# joint_board_boosterpack_can.net
KiCad netlist of a schematic drawn in Altium Designer
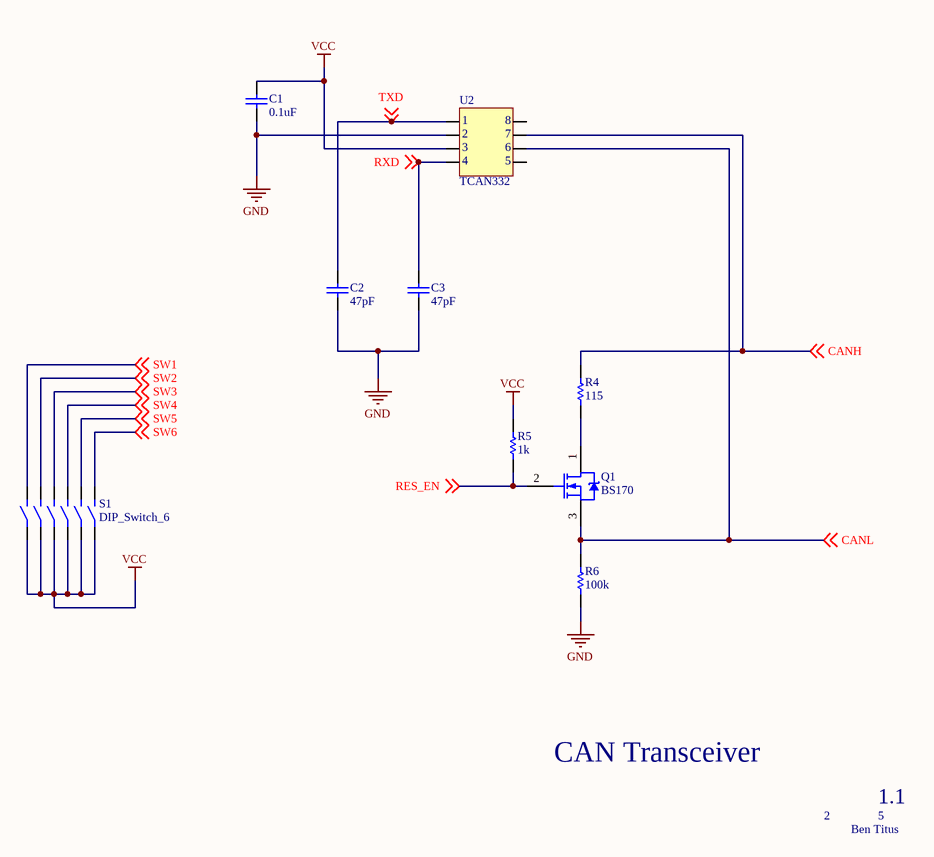
[diagram p0: joint_board_boosterpack_can.SchDoc]

(export (version "E")
  (design (tool "Eeschema 10.0.6"))
  (components
    (comp (ref "C1")
      (value "0.1uF")
      (footprint "CAPC0805(2012)145_L")
      (description "0805 (2012 Metric) Chip Capacitor")
      (libsource (lib "Altium Content Vault") (part "CAP_5"))
    )
    (comp (ref "C2")
      (value "47pF")
      (footprint "CAPC0805(2012)145_L")
      (description "0805 (2012 Metric) Chip Capacitor")
      (libsource (lib "Altium Content Vault") (part "CAP_5"))
    )
    (comp (ref "C3")
      (value "47pF")
      (footprint "CAPC0805(2012)145_L")
      (description "0805 (2012 Metric) Chip Capacitor")
      (libsource (lib "Altium Content Vault") (part "CAP_5"))
    )
    (comp (ref "Q1")
      (value "BS170")
      (footprint "SOT23-3")
      (description "Small Signal MOSFET, 500 mA, 60 V, N-Channel, 3-Pin TO-92, Bulk Box")
      (fields (field (name "MANUFACTURER") "On Semiconductor"))
      (libsource (lib "ON Semi MOSFETs") (part "BS170"))
    )
    (comp (ref "R4")
      (value "115")
      (footprint "RESC0805(2012)_L")
      (description "0805 (2012 Metric) Chip Resistor")
      (libsource (lib "Altium Content Vault") (part "RES_3"))
    )
    (comp (ref "R5")
      (value "1k")
      (footprint "RESC0805(2012)_L")
      (description "0805 (2012 Metric) Chip Resistor")
      (libsource (lib "Altium Content Vault") (part "RES_3"))
    )
    (comp (ref "R6")
      (value "100k")
      (footprint "RESC0805(2012)_L")
      (description "0805 (2012 Metric) Chip Resistor")
      (libsource (lib "Altium Content Vault") (part "RES_3"))
    )
    (comp (ref "S1")
      (value "DIP_Switch_6")
      (footprint "SOP12")
      (description "6 pin DIP switch")
      (libsource (lib "Custom_Lib") (part "DIP_Switch_6"))
    )
    (comp (ref "U2")
      (value "TCAN332")
      (footprint "SOP8")
      (description "3.3V CAN Transceiver")
      (libsource (lib "TCAN332") (part "TCAN332"))
    )
  )
  (nets
    (net (code "1") (name "CANH") (class "Default")
      (node (ref "R4") (pin "2") (pinfunction "2_2") (pintype "passive"))
      (node (ref "U2") (pin "7") (pintype "passive"))
    )
    (net (code "2") (name "CANL") (class "Default")
      (node (ref "Q1") (pin "3") (pinfunction "S_3") (pintype "passive"))
      (node (ref "R6") (pin "2") (pinfunction "2_2") (pintype "passive"))
      (node (ref "U2") (pin "6") (pintype "passive"))
    )
    (net (code "3") (name "GND") (class "Default")
      (node (ref "C1") (pin "1") (pinfunction "1_1") (pintype "passive"))
      (node (ref "C2") (pin "1") (pinfunction "1_1") (pintype "passive"))
      (node (ref "C3") (pin "1") (pinfunction "1_1") (pintype "passive"))
      (node (ref "R6") (pin "1") (pinfunction "1_1") (pintype "passive"))
      (node (ref "U2") (pin "2") (pintype "passive"))
    )
    (net (code "4") (name "Net-(Q1-D)") (class "Default")
      (node (ref "Q1") (pin "1") (pinfunction "D_1") (pintype "passive"))
      (node (ref "R4") (pin "1") (pinfunction "1_1") (pintype "passive"))
    )
    (net (code "5") (name "RES_EN") (class "Default")
      (node (ref "Q1") (pin "2") (pinfunction "G_2") (pintype "passive"))
      (node (ref "R5") (pin "1") (pinfunction "1_1") (pintype "passive"))
    )
    (net (code "6") (name "RXD") (class "Default")
      (node (ref "C3") (pin "2") (pinfunction "2_2") (pintype "passive"))
      (node (ref "U2") (pin "4") (pintype "passive"))
    )
    (net (code "7") (name "SW1") (class "Default") (node (ref "S1") (pin "12") (pintype "passive")))
    (net (code "8") (name "SW2") (class "Default") (node (ref "S1") (pin "11") (pintype "passive")))
    (net (code "9") (name "SW3") (class "Default") (node (ref "S1") (pin "10") (pintype "passive")))
    (net (code "10") (name "SW4") (class "Default") (node (ref "S1") (pin "9") (pintype "passive")))
    (net (code "11") (name "SW5") (class "Default") (node (ref "S1") (pin "8") (pintype "passive")))
    (net (code "12") (name "SW6") (class "Default") (node (ref "S1") (pin "7") (pintype "passive")))
    (net (code "13") (name "TXD") (class "Default")
      (node (ref "C2") (pin "2") (pinfunction "2_2") (pintype "passive"))
      (node (ref "U2") (pin "1") (pintype "passive"))
    )
    (net (code "14") (name "VCC") (class "Default")
      (node (ref "C1") (pin "2") (pinfunction "2_2") (pintype "passive"))
      (node (ref "R5") (pin "2") (pinfunction "2_2") (pintype "passive"))
      (node (ref "S1") (pin "1") (pintype "passive"))
      (node (ref "S1") (pin "2") (pintype "passive"))
      (node (ref "S1") (pin "3") (pintype "passive"))
      (node (ref "S1") (pin "4") (pintype "passive"))
      (node (ref "S1") (pin "5") (pintype "passive"))
      (node (ref "S1") (pin "6") (pintype "passive"))
      (node (ref "U2") (pin "3") (pintype "passive"))
    )
    (net (code "15") (name "unconnected-(U2-Pad5)") (class "Default")
      (node (ref "U2") (pin "5") (pintype "passive"))
    )
    (net (code "16") (name "unconnected-(U2-Pad8)") (class "Default")
      (node (ref "U2") (pin "8") (pintype "passive"))
    )
  )
)
